# LogicShifter.net
KiCad netlist of a schematic drawn in Altium Designer
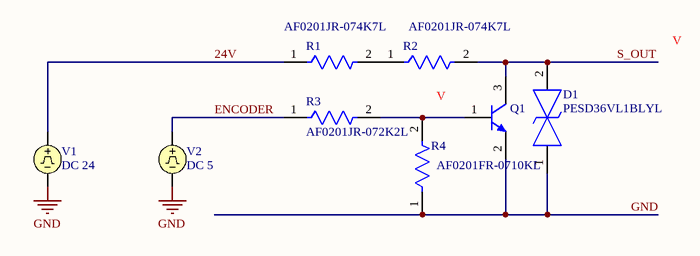
[diagram p0: LogicShifter.SchDoc]

(export (version "E")
  (design (tool "Eeschema 10.0.6"))
  (components
    (comp (ref "D1")
      (value "PESD36VL1BLYL")
      (footprint "SamacSys:PESD36VL1BLYL")
      (description "TVS Diode (Bi-directional)")
      (libsource (lib "SamacSys") (part "PESD36VL1BLYL"))
    )
    (comp (ref "Q1")
      (value "~")
      (footprint "INF-TSLP-3-1_V")
      (fields (field (name "MANUFACTURER") "Infineon") (field (name "PARTNUMBER") "BC847BL3"))
      (libsource (lib "Altium Content Vault") (part "INF-BJTNPN-BEC-3"))
    )
    (comp (ref "R1")
      (value "AF0201JR-074K7L")
      (footprint "FP-AF0201-IPC_B")
      (description "Anti-Sulfurated Chip Resistors Automotive Grade 4.7kΩ 5% 200ppm/°C 0201")
      (fields (field (name "TOLERANCE") "5%"))
      (libsource (lib "Altium Content Vault") (part "1029c3af85768c4190bb7ad29bc67b5"))
    )
    (comp (ref "R2")
      (value "AF0201JR-074K7L")
      (footprint "FP-AF0201-IPC_B")
      (description "Anti-Sulfurated Chip Resistors Automotive Grade 4.7kΩ 5% 200ppm/°C 0201")
      (fields (field (name "TOLERANCE") "5%"))
      (libsource (lib "Altium Content Vault") (part "1029c3af85768c4190bb7ad29bc67b5"))
    )
    (comp (ref "R3")
      (value "AF0201JR-072K2L")
      (footprint "FP-AF0201-IPC_B")
      (description "Anti-Sulfurated Chip Resistors Automotive Grade 2.2kΩ 5% 200ppm/°C 0201")
      (fields (field (name "TOLERANCE") "5%"))
      (libsource (lib "Altium Content Vault") (part "1029c3af85768c4190bb7ad29bc67b5"))
    )
    (comp (ref "R4")
      (value "AF0201FR-0710KL")
      (footprint "FP-AF0201-IPC_B")
      (description "Anti-Sulfurated Chip Resistors Automotive Grade 10kΩ 1% 200ppm/°C 0201")
      (fields (field (name "TOLERANCE") "1%"))
      (libsource (lib "Altium Content Vault") (part "1029c3af85768c4190bb7ad29bc67b5"))
    )
    (comp (ref "V1")
      (value "DC 24")
      (description "Pulse Voltage Source")
      (fields (field (name "PUBLISHER") "Altium Limited"))
      (libsource (lib "Simulation Generic Components") (part "VPULSE"))
    )
    (comp (ref "V2")
      (value "DC 5")
      (description "Pulse Voltage Source")
      (fields (field (name "PUBLISHER") "Altium Limited"))
      (libsource (lib "Simulation Generic Components") (part "VPULSE"))
    )
  )
  (nets
    (net (code "1") (name "/24V") (class "Default")
      (node (ref "R1") (pin "1") (pinfunction "1_1") (pintype "passive"))
      (node (ref "V1") (pin "1") (pinfunction "1_1") (pintype "passive"))
    )
    (net (code "2") (name "/ENCODER") (class "Default")
      (node (ref "R3") (pin "1") (pinfunction "1_1") (pintype "passive"))
      (node (ref "V2") (pin "1") (pinfunction "1_1") (pintype "passive"))
    )
    (net (code "3") (name "/S_OUT") (class "Default")
      (node (ref "D1") (pin "2") (pinfunction "2_2") (pintype "passive"))
      (node (ref "Q1") (pin "3") (pinfunction "C_3") (pintype "passive"))
      (node (ref "R2") (pin "2") (pinfunction "2_2") (pintype "passive"))
    )
    (net (code "4") (name "GND") (class "Default")
      (node (ref "D1") (pin "1") (pinfunction "1_1") (pintype "passive"))
      (node (ref "Q1") (pin "2") (pinfunction "E_2") (pintype "passive"))
      (node (ref "R4") (pin "1") (pinfunction "1_1") (pintype "passive"))
      (node (ref "V1") (pin "2") (pinfunction "2_2") (pintype "passive"))
      (node (ref "V2") (pin "2") (pinfunction "2_2") (pintype "passive"))
    )
    (net (code "5") (name "Net-(Q1-B)") (class "Default")
      (node (ref "Q1") (pin "1") (pinfunction "B_1") (pintype "passive"))
      (node (ref "R3") (pin "2") (pinfunction "2_2") (pintype "passive"))
      (node (ref "R4") (pin "2") (pinfunction "2_2") (pintype "passive"))
    )
    (net (code "6") (name "Net-(R1-Pad2)") (class "Default")
      (node (ref "R1") (pin "2") (pinfunction "2_2") (pintype "passive"))
      (node (ref "R2") (pin "1") (pinfunction "1_1") (pintype "passive"))
    )
  )
)
